# Safety_2019_V_3_0_BRAKE_LIGHT.net
KiCad netlist of a schematic drawn in Altium Designer
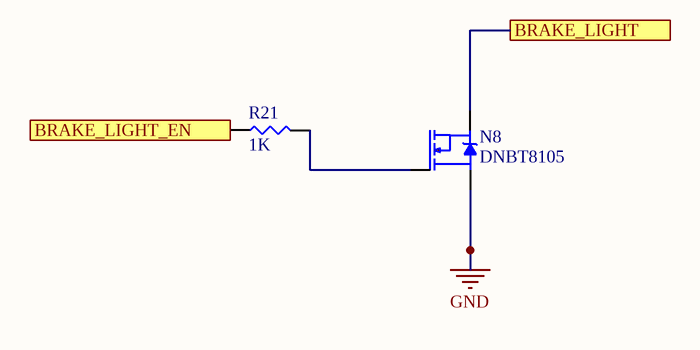
[diagram p0: Safety_2019_V_3_0_BRAKE_LIGHT.SchDoc]

(export (version "E")
  (design (tool "Eeschema 10.0.6"))
  (components
    (comp (ref "N8")
      (value "DNBT8105")
      (footprint "SOT23")
      (libsource (lib "ife19_Elec_Library") (part "NMOS-SOT23"))
    )
    (comp (ref "R21")
      (value "1K")
      (footprint "RES-0603")
      (libsource (lib "ife19_Elec_Library") (part "RES-0603"))
    )
  )
  (nets
    (net (code "1") (name "/BRAKE_LIGHT") (class "Default")
      (node (ref "N8") (pin "3") (pinfunction "D_3") (pintype "passive"))
    )
    (net (code "2") (name "/BRAKE_LIGHT_EN") (class "Default")
      (node (ref "R21") (pin "1") (pinfunction "1_1") (pintype "passive"))
    )
    (net (code "3") (name "GND") (class "Default")
      (node (ref "N8") (pin "2") (pinfunction "S_2") (pintype "passive"))
    )
    (net (code "4") (name "Net-(N8-G)") (class "Default")
      (node (ref "N8") (pin "1") (pinfunction "G_1") (pintype "passive"))
      (node (ref "R21") (pin "2") (pinfunction "2_2") (pintype "passive"))
    )
  )
)
